# 5V_Converter.net
KiCad netlist of a schematic drawn in Altium Designer
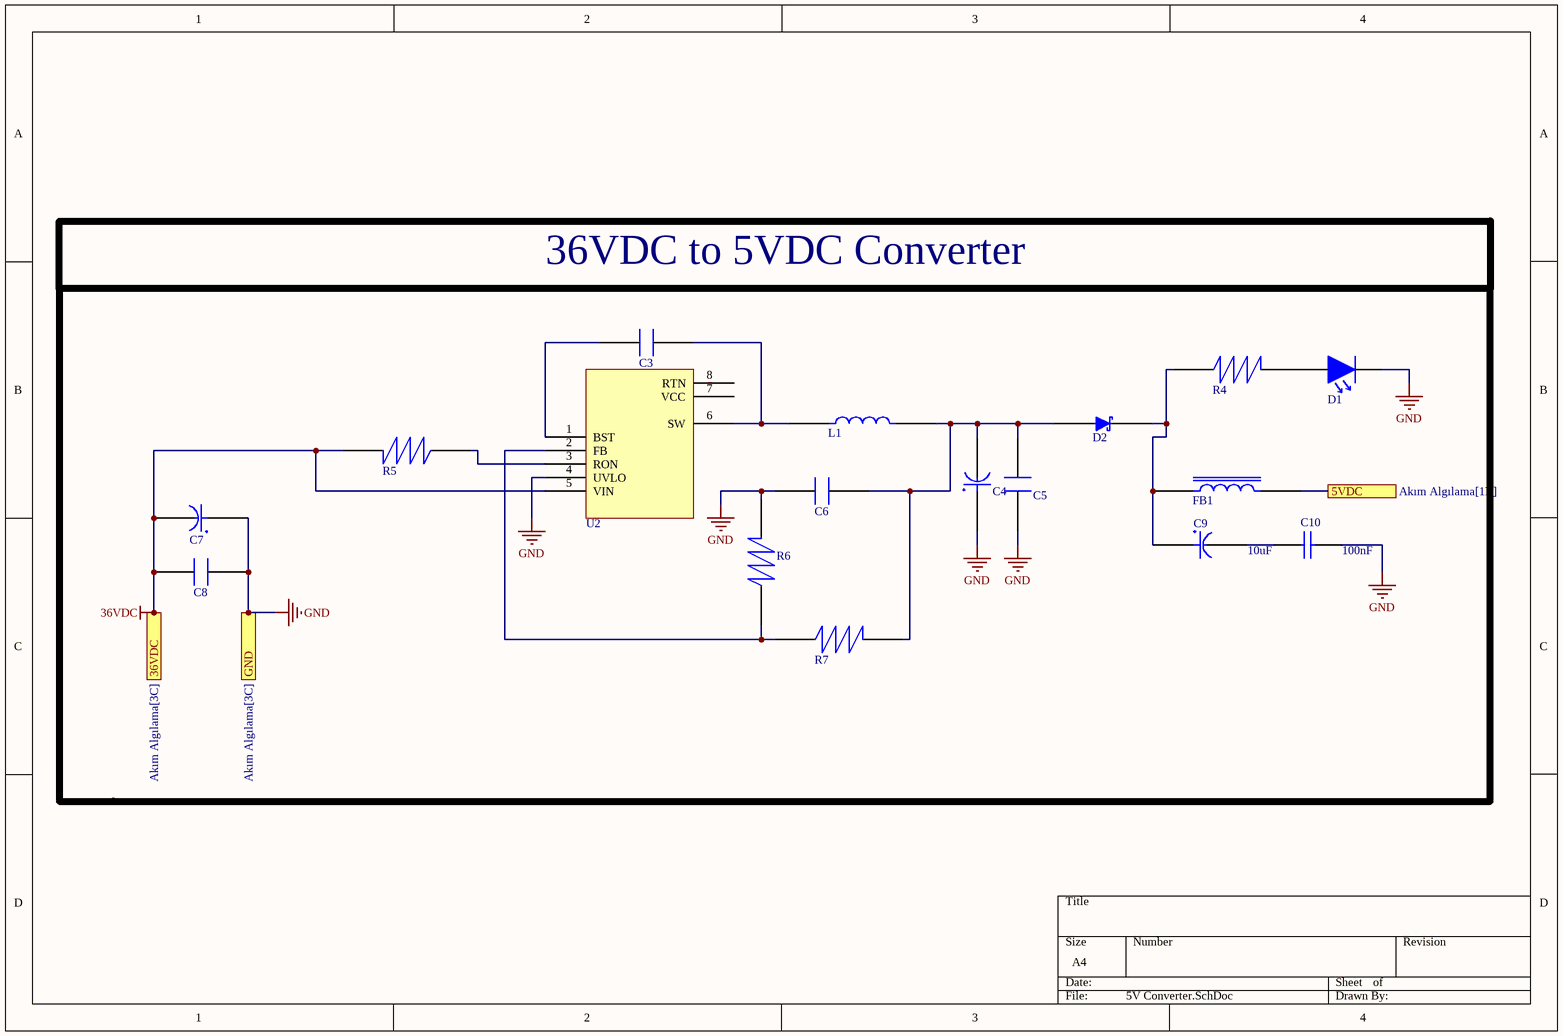
[diagram p0: 5V Converter.SchDoc]

(export (version "E")
  (design (tool "Eeschema 10.0.6"))
  (components
    (comp (ref "C3")
      (value "C0603C103F3GECAUTO")
      (footprint "CAP_0603")
      (description "CAP CER 10000PF 25V C0G/NP0 0603")
      (fields (field (name "MANUFACTURER") "KEMET") (field (name "DESIGNED BY") "ismet Akalın"))
      (libsource (lib "shunt") (part "C0603C103F3GECAUTO"))
    )
    (comp (ref "C4")
      (value "EEV226M025S9DAA")
      (footprint "EEV Series")
      (description "CAP ALUM 22UF 20% 25V SMD")
      (fields (field (name "MANUFACTURER") "KEMET") (field (name "DESIGNED BY") "ismet Akalın"))
      (libsource (lib "shunt") (part "EEV226M025S9DAA"))
    )
    (comp (ref "C5")
      (value "CL05B104KA5NNNC")
      (footprint "CAP_1005")
      (description "CAP CER 0.1UF 25V X7R 0402")
      (fields (field (name "MANUFACTURER") "Samsung") (field (name "DESIGNED BY") "ismet Akalın"))
      (libsource (lib "shunt") (part "CL05B104KA5NNNC"))
    )
    (comp (ref "C6")
      (value "CL05B104KA5NNNC")
      (footprint "CAP_1005")
      (description "CAP CER 0.1UF 25V X7R 0402")
      (fields (field (name "MANUFACTURER") "Samsung") (field (name "DESIGNED BY") "ismet Akalın"))
      (libsource (lib "shunt") (part "CL05B104KA5NNNC"))
    )
    (comp (ref "C7")
      (value "EEE-FK1H100UR")
      (footprint "CAP_RADIAL_EEE-FK1H100UR")
      (description "CAP ALUM 10UF 20% 50V SMD")
      (fields (field (name "MANUFACTURER") "Panasonic") (field (name "DESIGNED BY") "ismet Akalın"))
      (libsource (lib "shunt") (part "EEE-FK1H100UR"))
    )
    (comp (ref "C8")
      (value "KGM21NR71H104KT")
      (footprint "CAP_2012")
      (description "CAP CER 0.1UF 50V X7R 0805")
      (fields
        (field (name "MANUFACTURER") "Kyocera AVX")
        (field (name "MANUFACTURER PART NUMBER") "08055C104KAT2A")
        (field (name "DESIGNED BY") "ismet Akalın")
      )
      (libsource (lib "shunt") (part "KGM21NR71H104KT"))
    )
    (comp (ref "C9")
      (value "10uF")
      (footprint "CAP_TANTAL_1411 [3528 Metric]")
      (description "TANTAL CAP 10UF 10% 16V SMD 1411 [3528 Metric] Polarized")
      (fields
        (field (name "MANUFACTURER") "KEMET")
        (field (name "MANUFACTURER PART NUMBER") "T494B106K016AT")
        (field (name "DESIGNED BY") "ismet Akalın")
      )
      (libsource (lib "shunt") (part "T494B106K016AT"))
    )
    (comp (ref "C10")
      (value "C0603C104K5RACTU")
      (footprint "CAP_0603")
      (description "CAP CER 100nF %10 0603 SMD")
      (fields
        (field (name "MANUFACTURER") "KEMET")
        (field (name "TOLERANCE") "10%")
        (field (name "CAPACITANCE") "100nF")
        (field (name "DESIGNED BY") "BERK")
      )
      (libsource (lib "UDEMY_Library") (part "CAP CER 100nF 0603"))
    )
    (comp (ref "D1")
      (value "LTST-C171GKT")
      (footprint "LED_GREEN_0805")
      (description "Green 0805 130 º Min 5 mcd Typical 12 mcd Water Clear Lens SMT LED")
      (fields (field (name "MANUFACTURER") "Vishay Lite-On") (field (name "DESIGNED BY") "BERK"))
      (libsource (lib "UDEMY_Library") (part "LED GREEN 0805"))
    )
    (comp (ref "D2")
      (value "SS14")
      (footprint "SMA-2 (SS14)")
      (description "DIODE SCHOTTKY 40V 1A DO214AC")
      (fields
        (field (name "MANUFACTURER") "ON Semiconductor / Fairchild")
        (field (name "DESIGNED BY") "ismet Akalın")
      )
      (libsource (lib "shunt") (part "SS14"))
    )
    (comp (ref "FB1")
      (value "BLM21PG221SN1D")
      (footprint "CAP_0805")
      (description "FERRITE BEAD 220 OHM 0805 1LN")
      (fields (field (name "MANUFACTURER") "Murata") (field (name "DESIGNED BY") "ismet Akalın"))
      (libsource (lib "shunt") (part "BLM21PG221SN1D"))
    )
    (comp (ref "L1")
      (value "SRN8040-101M")
      (footprint "SRN8040-101M")
      (description "FIXED IND 100UH 1A 400 MOHM SMD")
      (fields
        (field (name "MANUFACTURER") "Bourns")
        (field (name "TOLERANCE") "20%")
        (field (name "DESIGNED BY") "ismet Akalın")
      )
      (libsource (lib "shunt") (part "SRN8040-101M"))
    )
    (comp (ref "R4")
      (value "CRG0603F330R")
      (footprint "RES_0603")
      (description "RES SMD 330 OHM 1% 1/10W 0603")
      (fields
        (field (name "MANUFACTURER") "TE Connectivity")
        (field (name "TOLERANCE") "1%")
        (field (name "DESIGNED BY") "ismet Akalın")
      )
      (libsource (lib "shunt") (part "CRG0603F330R"))
    )
    (comp (ref "R5")
      (value "ERJ-3EKF3303V")
      (footprint "RES_0603")
      (description "RES SMD 330K OHM 1% 1/10W 0603")
      (fields
        (field (name "MANUFACTURER") "Panasonic")
        (field (name "TOLERANCE") "1%")
        (field (name "DESIGNED BY") "ismet Akalın")
      )
      (libsource (lib "shunt") (part "ERJ-3EKF3303V"))
    )
    (comp (ref "R6")
      (value "RC0603FR-071K2L")
      (footprint "RES_0603")
      (description "RES 1.2K OHM 1% 1/10W 0603")
      (fields
        (field (name "MANUFACTURER") "Yageo")
        (field (name "TOLERANCE") "1%")
        (field (name "DESIGNED BY") "ismet Akalın")
      )
      (libsource (lib "shunt") (part "RC0603FR-071K2L"))
    )
    (comp (ref "R7")
      (value "RC0603FR-106K8L")
      (footprint "RES_0603")
      (description "RES 6.8K OHM 1% 1/10W 0603")
      (fields
        (field (name "MANUFACTURER") "Yageo")
        (field (name "TOLERANCE") "1%")
        (field (name "DESIGNED BY") "ismet Akalın")
      )
      (libsource (lib "shunt") (part "RC0603FR-106K8L"))
    )
    (comp (ref "U2")
      (value "LM5017MR/NOPB")
      (footprint "SOIC8")
      (description "IC REG BUCK ADJ 600MA 8SOPWR")
      (fields
        (field (name "MANUFACTURER") "TI National Semiconductor")
        (field (name "DESIGNED BY") "ismet Akalın")
      )
      (libsource (lib "shunt") (part "LM5017MR/NOPB"))
    )
  )
  (nets
    (net (code "1") (name "/5VDC") (class "Default")
      (node (ref "FB1") (pin "2") (pinfunction "2_2") (pintype "passive"))
    )
    (net (code "2") (name "36VDC") (class "Default")
      (node (ref "C7") (pin "2") (pinfunction "2_2") (pintype "passive"))
      (node (ref "C8") (pin "1") (pinfunction "1_1") (pintype "passive"))
      (node (ref "R5") (pin "2") (pinfunction "2_2") (pintype "passive"))
      (node (ref "U2") (pin "5") (pinfunction "VIN_5") (pintype "passive"))
    )
    (net (code "3") (name "GND") (class "Default")
      (node (ref "C10") (pin "2") (pinfunction "2_2") (pintype "passive"))
      (node (ref "C4") (pin "1") (pinfunction "1_1") (pintype "passive"))
      (node (ref "C5") (pin "2") (pinfunction "2_2") (pintype "passive"))
      (node (ref "C6") (pin "2") (pinfunction "2_2") (pintype "passive"))
      (node (ref "C7") (pin "1") (pinfunction "1_1") (pintype "passive"))
      (node (ref "C8") (pin "2") (pinfunction "2_2") (pintype "passive"))
      (node (ref "D1") (pin "1") (pinfunction "1_1") (pintype "power_in"))
      (node (ref "R6") (pin "2") (pinfunction "2_2") (pintype "passive"))
      (node (ref "U2") (pin "4") (pinfunction "UVLO_4") (pintype "passive"))
    )
    (net (code "4") (name "Net-(C4-Pad2)") (class "Default")
      (node (ref "C4") (pin "2") (pinfunction "2_2") (pintype "passive"))
      (node (ref "C5") (pin "1") (pinfunction "1_1") (pintype "passive"))
      (node (ref "C6") (pin "1") (pinfunction "1_1") (pintype "passive"))
      (node (ref "D2") (pin "2") (pinfunction "2_2") (pintype "passive"))
      (node (ref "L1") (pin "2") (pinfunction "2_2") (pintype "passive"))
      (node (ref "R7") (pin "2") (pinfunction "2_2") (pintype "passive"))
    )
    (net (code "5") (name "Net-(C9-Pad1)") (class "Default")
      (node (ref "C9") (pin "1") (pinfunction "1_1") (pintype "passive"))
      (node (ref "D2") (pin "1") (pinfunction "1_1") (pintype "passive"))
      (node (ref "FB1") (pin "1") (pinfunction "1_1") (pintype "passive"))
      (node (ref "R4") (pin "1") (pinfunction "1_1") (pintype "passive"))
    )
    (net (code "6") (name "Net-(C10-Pad1)") (class "Default")
      (node (ref "C10") (pin "1") (pinfunction "1_1") (pintype "passive"))
      (node (ref "C9") (pin "2") (pinfunction "2_2") (pintype "passive"))
    )
    (net (code "7") (name "Net-(D1-Pad2)") (class "Default")
      (node (ref "D1") (pin "2") (pinfunction "2_2") (pintype "power_in"))
      (node (ref "R4") (pin "2") (pinfunction "2_2") (pintype "passive"))
    )
    (net (code "8") (name "Net-(U2-BST)") (class "Default")
      (node (ref "C3") (pin "2") (pinfunction "2_2") (pintype "passive"))
      (node (ref "U2") (pin "1") (pinfunction "BST_1") (pintype "passive"))
    )
    (net (code "9") (name "Net-(U2-FB)") (class "Default")
      (node (ref "R6") (pin "1") (pinfunction "1_1") (pintype "passive"))
      (node (ref "R7") (pin "1") (pinfunction "1_1") (pintype "passive"))
      (node (ref "U2") (pin "2") (pinfunction "FB_2") (pintype "passive"))
    )
    (net (code "10") (name "Net-(U2-RON)") (class "Default")
      (node (ref "R5") (pin "1") (pinfunction "1_1") (pintype "passive"))
      (node (ref "U2") (pin "3") (pinfunction "RON_3") (pintype "passive"))
    )
    (net (code "11") (name "Net-(U2-SW)") (class "Default")
      (node (ref "C3") (pin "1") (pinfunction "1_1") (pintype "passive"))
      (node (ref "L1") (pin "1") (pinfunction "1_1") (pintype "passive"))
      (node (ref "U2") (pin "6") (pinfunction "SW_6") (pintype "passive"))
    )
    (net (code "12") (name "unconnected-(U2-RTN-Pad8)") (class "Default")
      (node (ref "U2") (pin "8") (pinfunction "RTN_8") (pintype "passive"))
    )
    (net (code "13") (name "unconnected-(U2-VCC-Pad7)") (class "Default")
      (node (ref "U2") (pin "7") (pinfunction "VCC_7") (pintype "passive"))
    )
  )
)
